# solenoid_driver.net
KiCad netlist of a schematic drawn in Altium Designer
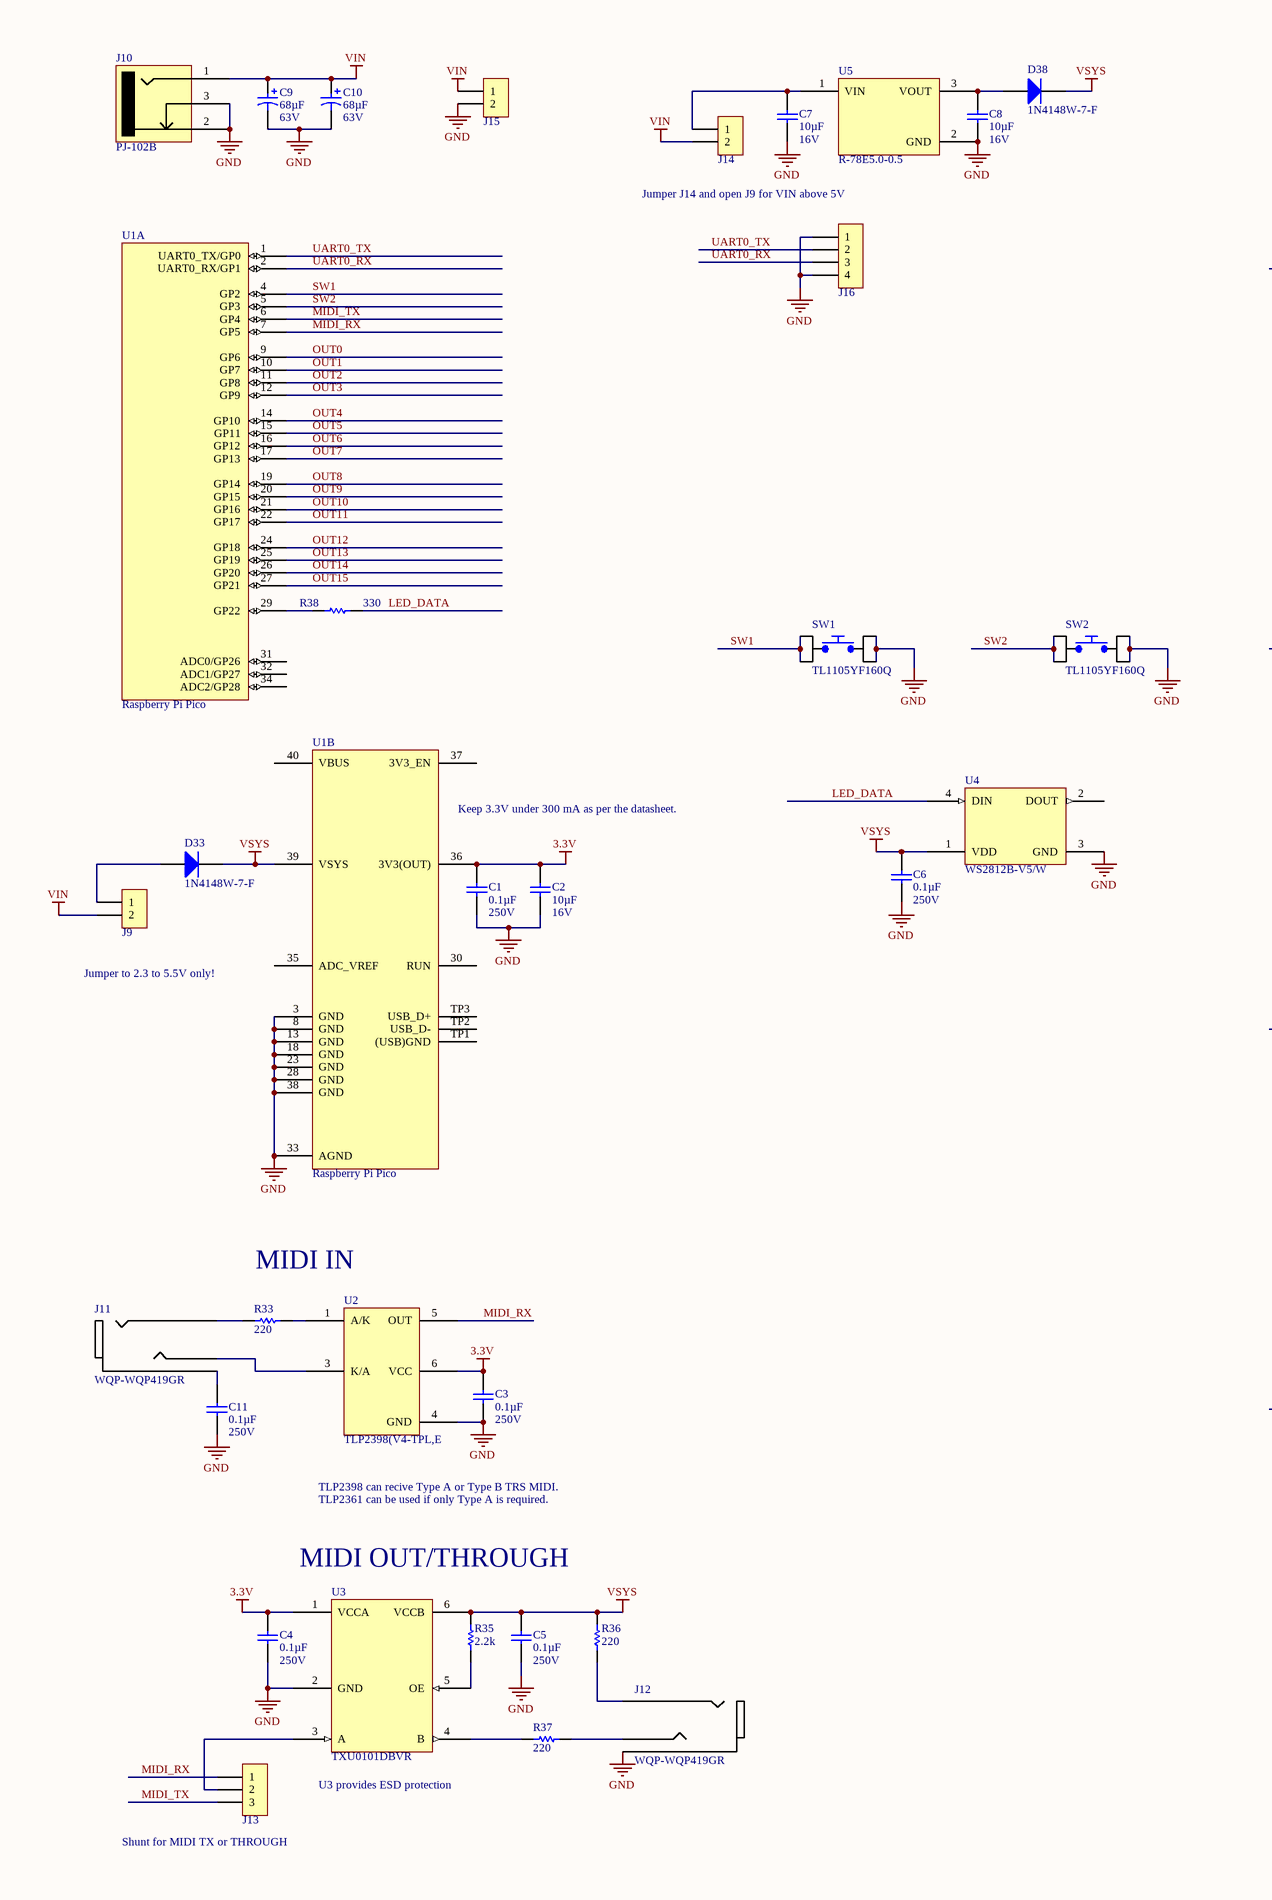
[diagram p0: solenoid_driver.SchDoc, left]
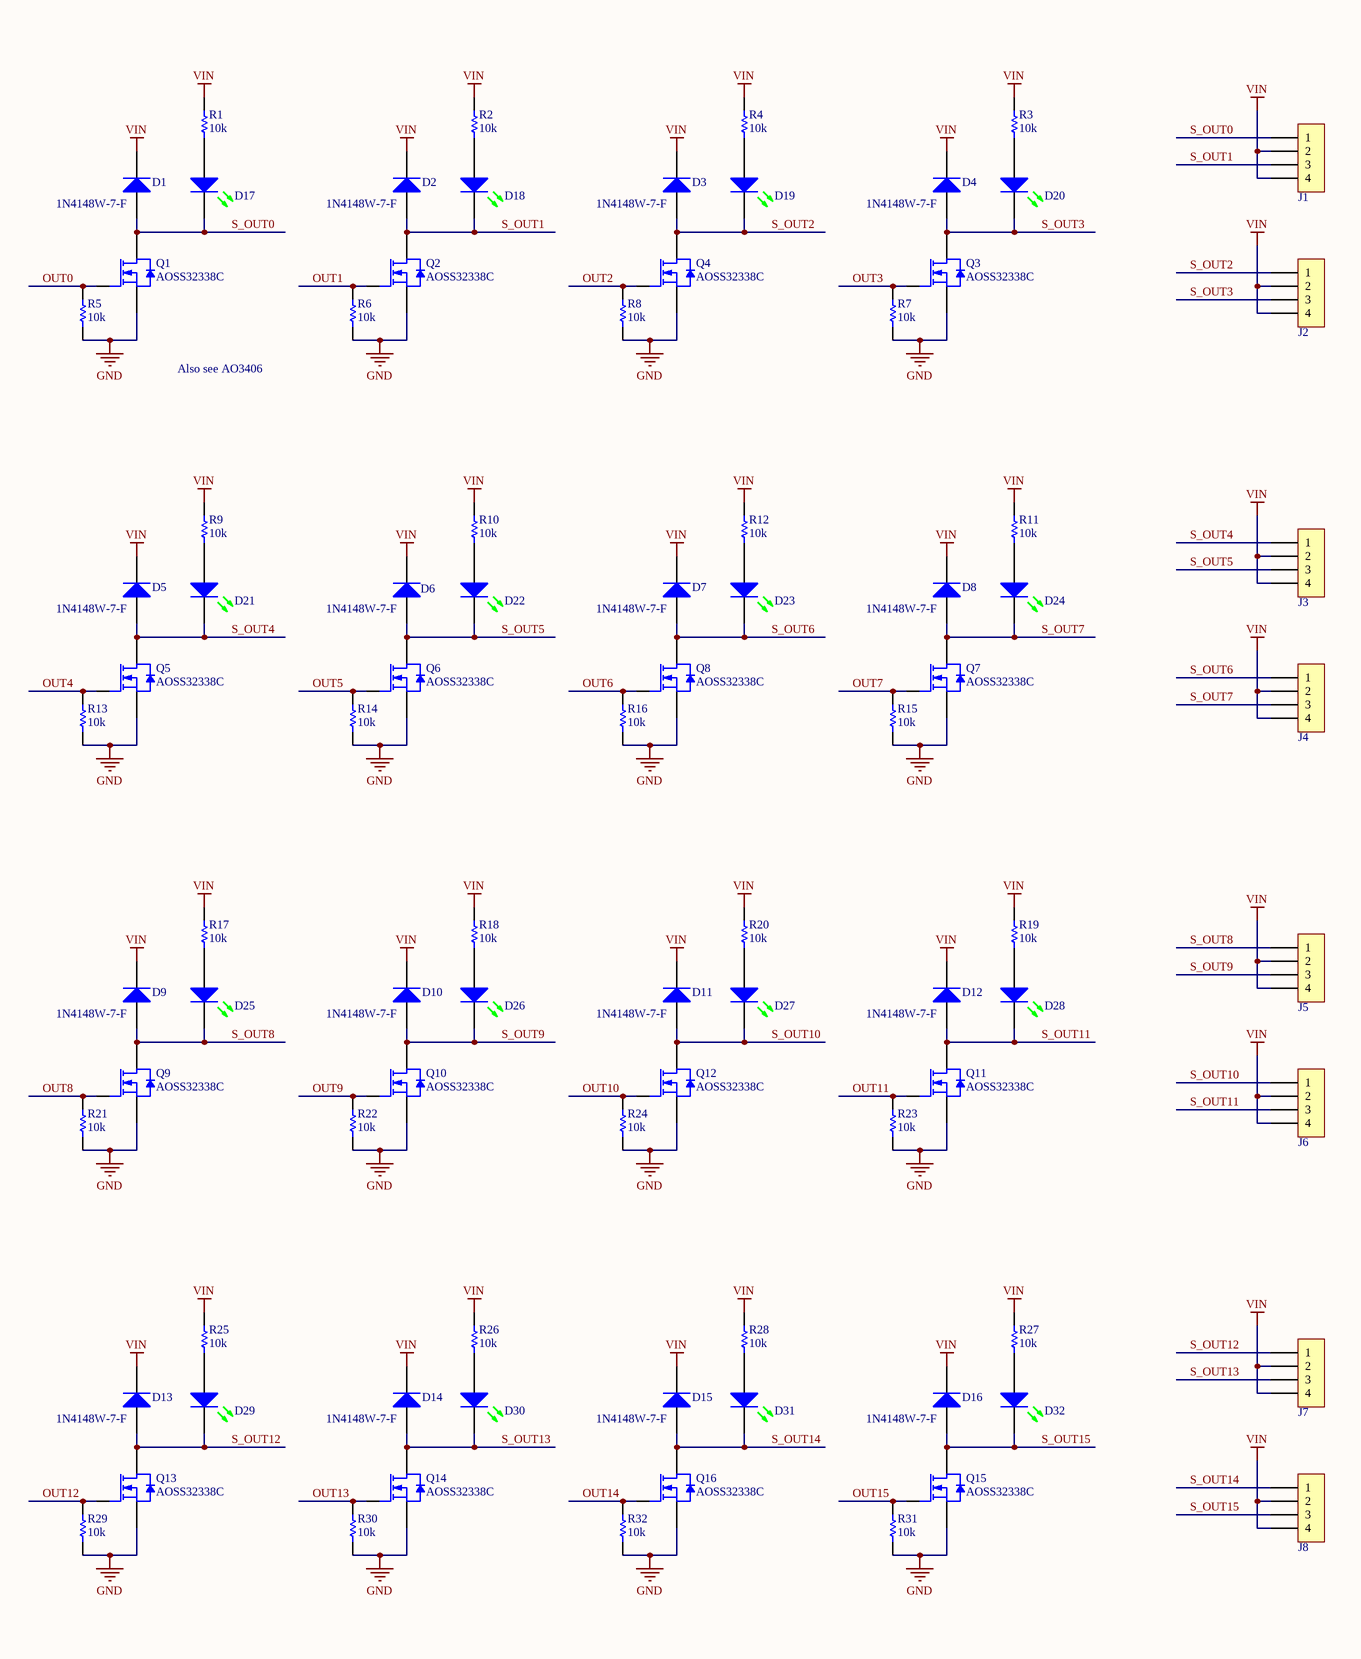
[diagram p1: solenoid_driver.SchDoc, right]

(export (version "E")
  (design (tool "Eeschema 10.0.6"))
  (components
    (comp (ref "C1")
      (value "0.1µF")
      (footprint "Chip0805")
      (description "CAP CER 0.1UF 250V 10% X7T 0805")
      (fields
        (field (name "VOLTAGE") "250V")
        (field (name "PARTNUMBER") "C2012X7T2E104K125AA")
        (field (name "MANUFACTURER") "TDK Corporation")
      )
      (libsource (lib "Passives") (part "CAP"))
    )
    (comp (ref "C2")
      (value "10µF")
      (footprint "Chip0805")
      (description "CAP CER 10UF 16V 10% X5R 0805")
      (fields
        (field (name "VOLTAGE") "16V")
        (field (name "PARTNUMBER") "C2012X5R1C106K125AC")
        (field (name "MANUFACTURER") "TDK Corporation")
      )
      (libsource (lib "Passives") (part "CAP"))
    )
    (comp (ref "C3")
      (value "0.1µF")
      (footprint "Chip0805")
      (description "CAP CER 0.1UF 250V 10% X7T 0805")
      (fields
        (field (name "VOLTAGE") "250V")
        (field (name "PARTNUMBER") "C2012X7T2E104K125AA")
        (field (name "MANUFACTURER") "TDK Corporation")
      )
      (libsource (lib "Passives") (part "CAP"))
    )
    (comp (ref "C4")
      (value "0.1µF")
      (footprint "Chip0805")
      (description "CAP CER 0.1UF 250V 10% X7T 0805")
      (fields
        (field (name "VOLTAGE") "250V")
        (field (name "PARTNUMBER") "C2012X7T2E104K125AA")
        (field (name "MANUFACTURER") "TDK Corporation")
      )
      (libsource (lib "Passives") (part "CAP"))
    )
    (comp (ref "C5")
      (value "0.1µF")
      (footprint "Chip0805")
      (description "CAP CER 0.1UF 250V 10% X7T 0805")
      (fields
        (field (name "VOLTAGE") "250V")
        (field (name "PARTNUMBER") "C2012X7T2E104K125AA")
        (field (name "MANUFACTURER") "TDK Corporation")
      )
      (libsource (lib "Passives") (part "CAP"))
    )
    (comp (ref "C6")
      (value "0.1µF")
      (footprint "Chip0805")
      (description "CAP CER 0.1UF 250V 10% X7T 0805")
      (fields
        (field (name "VOLTAGE") "250V")
        (field (name "PARTNUMBER") "C2012X7T2E104K125AA")
        (field (name "MANUFACTURER") "TDK Corporation")
      )
      (libsource (lib "Passives") (part "CAP"))
    )
    (comp (ref "C7")
      (value "10µF")
      (footprint "Chip0805")
      (description "CAP CER 10UF 16V 10% X5R 0805")
      (fields
        (field (name "VOLTAGE") "16V")
        (field (name "PARTNUMBER") "C2012X5R1C106K125AC")
        (field (name "MANUFACTURER") "TDK Corporation")
      )
      (libsource (lib "Passives") (part "CAP"))
    )
    (comp (ref "C8")
      (value "10µF")
      (footprint "Chip0805")
      (description "CAP CER 10UF 16V 10% X5R 0805")
      (fields
        (field (name "VOLTAGE") "16V")
        (field (name "PARTNUMBER") "C2012X5R1C106K125AC")
        (field (name "MANUFACTURER") "TDK Corporation")
      )
      (libsource (lib "Passives") (part "CAP"))
    )
    (comp (ref "C9")
      (value "68µF")
      (footprint "CAP_CAN_TH_3p5mmLS8")
      (description "CAP ALUM 68UF 20% 63V RADIAL")
      (fields
        (field (name "VOLTAGE RATING") "63V")
        (field (name "PARTNUMBER") "UPW1J680MPD")
        (field (name "MANUFACTURER") "Nichicon")
      )
      (libsource (lib "Passives") (part "CAP_POLARIZED"))
    )
    (comp (ref "C10")
      (value "68µF")
      (footprint "CAP_CAN_TH_3p5mmLS8")
      (description "CAP ALUM 68UF 20% 63V RADIAL")
      (fields
        (field (name "VOLTAGE RATING") "63V")
        (field (name "PARTNUMBER") "UPW1J680MPD")
        (field (name "MANUFACTURER") "Nichicon")
      )
      (libsource (lib "Passives") (part "CAP_POLARIZED"))
    )
    (comp (ref "C11")
      (value "0.1µF")
      (footprint "Chip0805")
      (description "CAP CER 0.1UF 250V 10% X7T 0805")
      (fields
        (field (name "VOLTAGE") "250V")
        (field (name "PARTNUMBER") "C2012X7T2E104K125AA")
        (field (name "MANUFACTURER") "TDK Corporation")
      )
      (libsource (lib "Passives") (part "CAP"))
    )
    (comp (ref "D1")
      (value "1N4148W-7-F")
      (footprint "SOD-123")
      (description "DIODE SWITCH 100V 0.15A SOD123")
      (fields (field (name "MANUFACTURER") "Diodes Incorporated"))
      (libsource (lib "Semiconductor") (part "DIODE"))
    )
    (comp (ref "D2")
      (value "1N4148W-7-F")
      (footprint "SOD-123")
      (description "DIODE SWITCH 100V 0.15A SOD123")
      (fields (field (name "MANUFACTURER") "Diodes Incorporated"))
      (libsource (lib "Semiconductor") (part "DIODE"))
    )
    (comp (ref "D3")
      (value "1N4148W-7-F")
      (footprint "SOD-123")
      (description "DIODE SWITCH 100V 0.15A SOD123")
      (fields (field (name "MANUFACTURER") "Diodes Incorporated"))
      (libsource (lib "Semiconductor") (part "DIODE"))
    )
    (comp (ref "D4")
      (value "1N4148W-7-F")
      (footprint "SOD-123")
      (description "DIODE SWITCH 100V 0.15A SOD123")
      (fields (field (name "MANUFACTURER") "Diodes Incorporated"))
      (libsource (lib "Semiconductor") (part "DIODE"))
    )
    (comp (ref "D5")
      (value "1N4148W-7-F")
      (footprint "SOD-123")
      (description "DIODE SWITCH 100V 0.15A SOD123")
      (fields (field (name "MANUFACTURER") "Diodes Incorporated"))
      (libsource (lib "Semiconductor") (part "DIODE"))
    )
    (comp (ref "D6")
      (value "1N4148W-7-F")
      (footprint "SOD-123")
      (description "DIODE SWITCH 100V 0.15A SOD123")
      (fields (field (name "MANUFACTURER") "Diodes Incorporated"))
      (libsource (lib "Semiconductor") (part "DIODE"))
    )
    (comp (ref "D7")
      (value "1N4148W-7-F")
      (footprint "SOD-123")
      (description "DIODE SWITCH 100V 0.15A SOD123")
      (fields (field (name "MANUFACTURER") "Diodes Incorporated"))
      (libsource (lib "Semiconductor") (part "DIODE"))
    )
    (comp (ref "D8")
      (value "1N4148W-7-F")
      (footprint "SOD-123")
      (description "DIODE SWITCH 100V 0.15A SOD123")
      (fields (field (name "MANUFACTURER") "Diodes Incorporated"))
      (libsource (lib "Semiconductor") (part "DIODE"))
    )
    (comp (ref "D9")
      (value "1N4148W-7-F")
      (footprint "SOD-123")
      (description "DIODE SWITCH 100V 0.15A SOD123")
      (fields (field (name "MANUFACTURER") "Diodes Incorporated"))
      (libsource (lib "Semiconductor") (part "DIODE"))
    )
    (comp (ref "D10")
      (value "1N4148W-7-F")
      (footprint "SOD-123")
      (description "DIODE SWITCH 100V 0.15A SOD123")
      (fields (field (name "MANUFACTURER") "Diodes Incorporated"))
      (libsource (lib "Semiconductor") (part "DIODE"))
    )
    (comp (ref "D11")
      (value "1N4148W-7-F")
      (footprint "SOD-123")
      (description "DIODE SWITCH 100V 0.15A SOD123")
      (fields (field (name "MANUFACTURER") "Diodes Incorporated"))
      (libsource (lib "Semiconductor") (part "DIODE"))
    )
    (comp (ref "D12")
      (value "1N4148W-7-F")
      (footprint "SOD-123")
      (description "DIODE SWITCH 100V 0.15A SOD123")
      (fields (field (name "MANUFACTURER") "Diodes Incorporated"))
      (libsource (lib "Semiconductor") (part "DIODE"))
    )
    (comp (ref "D13")
      (value "1N4148W-7-F")
      (footprint "SOD-123")
      (description "DIODE SWITCH 100V 0.15A SOD123")
      (fields (field (name "MANUFACTURER") "Diodes Incorporated"))
      (libsource (lib "Semiconductor") (part "DIODE"))
    )
    (comp (ref "D14")
      (value "1N4148W-7-F")
      (footprint "SOD-123")
      (description "DIODE SWITCH 100V 0.15A SOD123")
      (fields (field (name "MANUFACTURER") "Diodes Incorporated"))
      (libsource (lib "Semiconductor") (part "DIODE"))
    )
    (comp (ref "D15")
      (value "1N4148W-7-F")
      (footprint "SOD-123")
      (description "DIODE SWITCH 100V 0.15A SOD123")
      (fields (field (name "MANUFACTURER") "Diodes Incorporated"))
      (libsource (lib "Semiconductor") (part "DIODE"))
    )
    (comp (ref "D16")
      (value "1N4148W-7-F")
      (footprint "SOD-123")
      (description "DIODE SWITCH 100V 0.15A SOD123")
      (fields (field (name "MANUFACTURER") "Diodes Incorporated"))
      (libsource (lib "Semiconductor") (part "DIODE"))
    )
    (comp (ref "D17")
      (value "GREEN")
      (footprint "LED0603")
      (description "LED GREEN CLEAR THIN 0603 SMD")
      (fields (field (name "PARTNUMBER") "LTST-C191GKT") (field (name "MANUFACTURER") "Lite-On Inc"))
      (libsource (lib "Optoelectronics") (part "LED_GREEN"))
    )
    (comp (ref "D18")
      (value "GREEN")
      (footprint "LED0603")
      (description "LED GREEN CLEAR THIN 0603 SMD")
      (fields (field (name "PARTNUMBER") "LTST-C191GKT") (field (name "MANUFACTURER") "Lite-On Inc"))
      (libsource (lib "Optoelectronics") (part "LED_GREEN"))
    )
    (comp (ref "D19")
      (value "GREEN")
      (footprint "LED0603")
      (description "LED GREEN CLEAR THIN 0603 SMD")
      (fields (field (name "PARTNUMBER") "LTST-C191GKT") (field (name "MANUFACTURER") "Lite-On Inc"))
      (libsource (lib "Optoelectronics") (part "LED_GREEN"))
    )
    (comp (ref "D20")
      (value "GREEN")
      (footprint "LED0603")
      (description "LED GREEN CLEAR THIN 0603 SMD")
      (fields (field (name "PARTNUMBER") "LTST-C191GKT") (field (name "MANUFACTURER") "Lite-On Inc"))
      (libsource (lib "Optoelectronics") (part "LED_GREEN"))
    )
    (comp (ref "D21")
      (value "GREEN")
      (footprint "LED0603")
      (description "LED GREEN CLEAR THIN 0603 SMD")
      (fields (field (name "PARTNUMBER") "LTST-C191GKT") (field (name "MANUFACTURER") "Lite-On Inc"))
      (libsource (lib "Optoelectronics") (part "LED_GREEN"))
    )
    (comp (ref "D22")
      (value "GREEN")
      (footprint "LED0603")
      (description "LED GREEN CLEAR THIN 0603 SMD")
      (fields (field (name "PARTNUMBER") "LTST-C191GKT") (field (name "MANUFACTURER") "Lite-On Inc"))
      (libsource (lib "Optoelectronics") (part "LED_GREEN"))
    )
    (comp (ref "D23")
      (value "GREEN")
      (footprint "LED0603")
      (description "LED GREEN CLEAR THIN 0603 SMD")
      (fields (field (name "PARTNUMBER") "LTST-C191GKT") (field (name "MANUFACTURER") "Lite-On Inc"))
      (libsource (lib "Optoelectronics") (part "LED_GREEN"))
    )
    (comp (ref "D24")
      (value "GREEN")
      (footprint "LED0603")
      (description "LED GREEN CLEAR THIN 0603 SMD")
      (fields (field (name "PARTNUMBER") "LTST-C191GKT") (field (name "MANUFACTURER") "Lite-On Inc"))
      (libsource (lib "Optoelectronics") (part "LED_GREEN"))
    )
    (comp (ref "D25")
      (value "GREEN")
      (footprint "LED0603")
      (description "LED GREEN CLEAR THIN 0603 SMD")
      (fields (field (name "PARTNUMBER") "LTST-C191GKT") (field (name "MANUFACTURER") "Lite-On Inc"))
      (libsource (lib "Optoelectronics") (part "LED_GREEN"))
    )
    (comp (ref "D26")
      (value "GREEN")
      (footprint "LED0603")
      (description "LED GREEN CLEAR THIN 0603 SMD")
      (fields (field (name "PARTNUMBER") "LTST-C191GKT") (field (name "MANUFACTURER") "Lite-On Inc"))
      (libsource (lib "Optoelectronics") (part "LED_GREEN"))
    )
    (comp (ref "D27")
      (value "GREEN")
      (footprint "LED0603")
      (description "LED GREEN CLEAR THIN 0603 SMD")
      (fields (field (name "PARTNUMBER") "LTST-C191GKT") (field (name "MANUFACTURER") "Lite-On Inc"))
      (libsource (lib "Optoelectronics") (part "LED_GREEN"))
    )
    (comp (ref "D28")
      (value "GREEN")
      (footprint "LED0603")
      (description "LED GREEN CLEAR THIN 0603 SMD")
      (fields (field (name "PARTNUMBER") "LTST-C191GKT") (field (name "MANUFACTURER") "Lite-On Inc"))
      (libsource (lib "Optoelectronics") (part "LED_GREEN"))
    )
    (comp (ref "D29")
      (value "GREEN")
      (footprint "LED0603")
      (description "LED GREEN CLEAR THIN 0603 SMD")
      (fields (field (name "PARTNUMBER") "LTST-C191GKT") (field (name "MANUFACTURER") "Lite-On Inc"))
      (libsource (lib "Optoelectronics") (part "LED_GREEN"))
    )
    (comp (ref "D30")
      (value "GREEN")
      (footprint "LED0603")
      (description "LED GREEN CLEAR THIN 0603 SMD")
      (fields (field (name "PARTNUMBER") "LTST-C191GKT") (field (name "MANUFACTURER") "Lite-On Inc"))
      (libsource (lib "Optoelectronics") (part "LED_GREEN"))
    )
    (comp (ref "D31")
      (value "GREEN")
      (footprint "LED0603")
      (description "LED GREEN CLEAR THIN 0603 SMD")
      (fields (field (name "PARTNUMBER") "LTST-C191GKT") (field (name "MANUFACTURER") "Lite-On Inc"))
      (libsource (lib "Optoelectronics") (part "LED_GREEN"))
    )
    (comp (ref "D32")
      (value "GREEN")
      (footprint "LED0603")
      (description "LED GREEN CLEAR THIN 0603 SMD")
      (fields (field (name "PARTNUMBER") "LTST-C191GKT") (field (name "MANUFACTURER") "Lite-On Inc"))
      (libsource (lib "Optoelectronics") (part "LED_GREEN"))
    )
    (comp (ref "D33")
      (value "1N4148W-7-F")
      (footprint "SOD-123")
      (description "DIODE SWITCH 100V 0.15A SOD123")
      (fields (field (name "MANUFACTURER") "Diodes Incorporated"))
      (libsource (lib "Semiconductor") (part "DIODE"))
    )
    (comp (ref "D38")
      (value "1N4148W-7-F")
      (footprint "SOD-123")
      (description "DIODE SWITCH 100V 0.15A SOD123")
      (fields (field (name "MANUFACTURER") "Diodes Incorporated"))
      (libsource (lib "Semiconductor") (part "DIODE"))
    )
    (comp (ref "J1")
      (value "691210910004")
      (footprint "WURTH_691210910004")
      (description "TERM BLOCK 4P HORIZON 2.54MM PCB")
      (fields (field (name "MANUFACTURER") "Würth Elektronik"))
      (libsource (lib "Connectors") (part "HEADER_1x4"))
    )
    (comp (ref "J2")
      (value "691210910004")
      (footprint "WURTH_691210910004")
      (description "TERM BLOCK 4P HORIZON 2.54MM PCB")
      (fields (field (name "MANUFACTURER") "Würth Elektronik"))
      (libsource (lib "Connectors") (part "HEADER_1x4"))
    )
    (comp (ref "J3")
      (value "691210910004")
      (footprint "WURTH_691210910004")
      (description "TERM BLOCK 4P HORIZON 2.54MM PCB")
      (fields (field (name "MANUFACTURER") "Würth Elektronik"))
      (libsource (lib "Connectors") (part "HEADER_1x4"))
    )
    (comp (ref "J4")
      (value "691210910004")
      (footprint "WURTH_691210910004")
      (description "TERM BLOCK 4P HORIZON 2.54MM PCB")
      (fields (field (name "MANUFACTURER") "Würth Elektronik"))
      (libsource (lib "Connectors") (part "HEADER_1x4"))
    )
    (comp (ref "J5")
      (value "691210910004")
      (footprint "WURTH_691210910004")
      (description "TERM BLOCK 4P HORIZON 2.54MM PCB")
      (fields (field (name "MANUFACTURER") "Würth Elektronik"))
      (libsource (lib "Connectors") (part "HEADER_1x4"))
    )
    (comp (ref "J6")
      (value "691210910004")
      (footprint "WURTH_691210910004")
      (description "TERM BLOCK 4P HORIZON 2.54MM PCB")
      (fields (field (name "MANUFACTURER") "Würth Elektronik"))
      (libsource (lib "Connectors") (part "HEADER_1x4"))
    )
    (comp (ref "J7")
      (value "691210910004")
      (footprint "WURTH_691210910004")
      (description "TERM BLOCK 4P HORIZON 2.54MM PCB")
      (fields (field (name "MANUFACTURER") "Würth Elektronik"))
      (libsource (lib "Connectors") (part "HEADER_1x4"))
    )
    (comp (ref "J8")
      (value "691210910004")
      (footprint "WURTH_691210910004")
      (description "TERM BLOCK 4P HORIZON 2.54MM PCB")
      (fields (field (name "MANUFACTURER") "Würth Elektronik"))
      (libsource (lib "Connectors") (part "HEADER_1x4"))
    )
    (comp (ref "J9")
      (value "3-644456-2")
      (footprint "TE_3-644456-2")
      (description "CONN HEADER VERT 2POS .100 TIN")
      (fields (field (name "MANUFACTURER") "TE Connectivity"))
      (libsource (lib "Connectors") (part "HEADER_1x2"))
    )
    (comp (ref "J10")
      (value "PJ-102B")
      (footprint "CUI_PJ-102B")
      (description "CONN PWR JACK 2.5X5.5MM SOLDER")
      (fields (field (name "MANUFACTURER") "CUI Devices"))
      (libsource (lib "Connectors") (part "DC_POWER_JACK"))
    )
    (comp (ref "J11")
      (value "WQP-WQP419GR")
      (footprint "PJ366ST")
      (description "CONN 3.5mm VIRTICAL STEREO")
      (fields (field (name "MANUFACTURER") "QingPu"))
      (libsource (lib "Connectors") (part "PJ366ST"))
    )
    (comp (ref "J12")
      (value "WQP-WQP419GR")
      (footprint "PJ366ST")
      (description "CONN 3.5mm VIRTICAL STEREO")
      (fields (field (name "MANUFACTURER") "QingPu"))
      (libsource (lib "Connectors") (part "PJ366ST"))
    )
    (comp (ref "J13")
      (value "3-644456-3")
      (footprint "TE_3-644456-3")
      (description "CONN HEADER VERT 3POS .100 TIN")
      (fields (field (name "MANUFACTURER") "TE Connectivity"))
      (libsource (lib "Connectors") (part "HEADER_1x3"))
    )
    (comp (ref "J14")
      (value "3-644456-2")
      (footprint "TE_3-644456-2")
      (description "CONN HEADER VERT 2POS .100 TIN")
      (fields (field (name "MANUFACTURER") "TE Connectivity"))
      (libsource (lib "Connectors") (part "HEADER_1x2"))
    )
    (comp (ref "J15")
      (value "691210910002")
      (footprint "WURTH_691210910002")
      (description "TERM BLOCK 2P HORIZON 2.54MM PCB")
      (fields (field (name "MANUFACTURER") "Würth Elektronik"))
      (libsource (lib "Connectors") (part "HEADER_1x2"))
    )
    (comp (ref "J16")
      (value "0533980471")
      (footprint "Molex_0533980471")
      (description "CONN HEADER SMD 4POS 1.25MM")
      (fields (field (name "MANUFACTURER") "Molex"))
      (libsource (lib "Connectors") (part "HEADER_1x4"))
    )
    (comp (ref "Q1")
      (value "AOSS32338C")
      (footprint "SOT23-3N")
      (description "MOSFET N-CH 30V 4A SOT23-3")
      (fields (field (name "MANUFACTURER") "Alpha & Omega Semiconductor Inc."))
      (libsource (lib "Semiconductor") (part "FET_N_ENHANCEMENT"))
    )
    (comp (ref "Q2")
      (value "AOSS32338C")
      (footprint "SOT23-3N")
      (description "MOSFET N-CH 30V 4A SOT23-3")
      (fields (field (name "MANUFACTURER") "Alpha & Omega Semiconductor Inc."))
      (libsource (lib "Semiconductor") (part "FET_N_ENHANCEMENT"))
    )
    (comp (ref "Q3")
      (value "AOSS32338C")
      (footprint "SOT23-3N")
      (description "MOSFET N-CH 30V 4A SOT23-3")
      (fields (field (name "MANUFACTURER") "Alpha & Omega Semiconductor Inc."))
      (libsource (lib "Semiconductor") (part "FET_N_ENHANCEMENT"))
    )
    (comp (ref "Q4")
      (value "AOSS32338C")
      (footprint "SOT23-3N")
      (description "MOSFET N-CH 30V 4A SOT23-3")
      (fields (field (name "MANUFACTURER") "Alpha & Omega Semiconductor Inc."))
      (libsource (lib "Semiconductor") (part "FET_N_ENHANCEMENT"))
    )
    (comp (ref "Q5")
      (value "AOSS32338C")
      (footprint "SOT23-3N")
      (description "MOSFET N-CH 30V 4A SOT23-3")
      (fields (field (name "MANUFACTURER") "Alpha & Omega Semiconductor Inc."))
      (libsource (lib "Semiconductor") (part "FET_N_ENHANCEMENT"))
    )
    (comp (ref "Q6")
      (value "AOSS32338C")
      (footprint "SOT23-3N")
      (description "MOSFET N-CH 30V 4A SOT23-3")
      (fields (field (name "MANUFACTURER") "Alpha & Omega Semiconductor Inc."))
      (libsource (lib "Semiconductor") (part "FET_N_ENHANCEMENT"))
    )
    (comp (ref "Q7")
      (value "AOSS32338C")
      (footprint "SOT23-3N")
      (description "MOSFET N-CH 30V 4A SOT23-3")
      (fields (field (name "MANUFACTURER") "Alpha & Omega Semiconductor Inc."))
      (libsource (lib "Semiconductor") (part "FET_N_ENHANCEMENT"))
    )
    (comp (ref "Q8")
      (value "AOSS32338C")
      (footprint "SOT23-3N")
      (description "MOSFET N-CH 30V 4A SOT23-3")
      (fields (field (name "MANUFACTURER") "Alpha & Omega Semiconductor Inc."))
      (libsource (lib "Semiconductor") (part "FET_N_ENHANCEMENT"))
    )
    (comp (ref "Q9")
      (value "AOSS32338C")
      (footprint "SOT23-3N")
      (description "MOSFET N-CH 30V 4A SOT23-3")
      (fields (field (name "MANUFACTURER") "Alpha & Omega Semiconductor Inc."))
      (libsource (lib "Semiconductor") (part "FET_N_ENHANCEMENT"))
    )
    (comp (ref "Q10")
      (value "AOSS32338C")
      (footprint "SOT23-3N")
      (description "MOSFET N-CH 30V 4A SOT23-3")
      (fields (field (name "MANUFACTURER") "Alpha & Omega Semiconductor Inc."))
      (libsource (lib "Semiconductor") (part "FET_N_ENHANCEMENT"))
    )
    (comp (ref "Q11")
      (value "AOSS32338C")
      (footprint "SOT23-3N")
      (description "MOSFET N-CH 30V 4A SOT23-3")
      (fields (field (name "MANUFACTURER") "Alpha & Omega Semiconductor Inc."))
      (libsource (lib "Semiconductor") (part "FET_N_ENHANCEMENT"))
    )
    (comp (ref "Q12")
      (value "AOSS32338C")
      (footprint "SOT23-3N")
      (description "MOSFET N-CH 30V 4A SOT23-3")
      (fields (field (name "MANUFACTURER") "Alpha & Omega Semiconductor Inc."))
      (libsource (lib "Semiconductor") (part "FET_N_ENHANCEMENT"))
    )
    (comp (ref "Q13")
      (value "AOSS32338C")
      (footprint "SOT23-3N")
      (description "MOSFET N-CH 30V 4A SOT23-3")
      (fields (field (name "MANUFACTURER") "Alpha & Omega Semiconductor Inc."))
      (libsource (lib "Semiconductor") (part "FET_N_ENHANCEMENT"))
    )
    (comp (ref "Q14")
      (value "AOSS32338C")
      (footprint "SOT23-3N")
      (description "MOSFET N-CH 30V 4A SOT23-3")
      (fields (field (name "MANUFACTURER") "Alpha & Omega Semiconductor Inc."))
      (libsource (lib "Semiconductor") (part "FET_N_ENHANCEMENT"))
    )
    (comp (ref "Q15")
      (value "AOSS32338C")
      (footprint "SOT23-3N")
      (description "MOSFET N-CH 30V 4A SOT23-3")
      (fields (field (name "MANUFACTURER") "Alpha & Omega Semiconductor Inc."))
      (libsource (lib "Semiconductor") (part "FET_N_ENHANCEMENT"))
    )
    (comp (ref "Q16")
      (value "AOSS32338C")
      (footprint "SOT23-3N")
      (description "MOSFET N-CH 30V 4A SOT23-3")
      (fields (field (name "MANUFACTURER") "Alpha & Omega Semiconductor Inc."))
      (libsource (lib "Semiconductor") (part "FET_N_ENHANCEMENT"))
    )
    (comp (ref "R1")
      (value "10k")
      (footprint "Chip0805")
      (description "RES 10.0K OHM 1/8W 1% 0805 SMD")
      (fields (field (name "PARTNUMBER") "CRCW080510K0FKEA") (field (name "MANUFACTURER") "Vishay Dale"))
      (libsource (lib "Passives") (part "RES"))
    )
    (comp (ref "R2")
      (value "10k")
      (footprint "Chip0805")
      (description "RES 10.0K OHM 1/8W 1% 0805 SMD")
      (fields (field (name "PARTNUMBER") "CRCW080510K0FKEA") (field (name "MANUFACTURER") "Vishay Dale"))
      (libsource (lib "Passives") (part "RES"))
    )
    (comp (ref "R3")
      (value "10k")
      (footprint "Chip0805")
      (description "RES 10.0K OHM 1/8W 1% 0805 SMD")
      (fields (field (name "PARTNUMBER") "CRCW080510K0FKEA") (field (name "MANUFACTURER") "Vishay Dale"))
      (libsource (lib "Passives") (part "RES"))
    )
    (comp (ref "R4")
      (value "10k")
      (footprint "Chip0805")
      (description "RES 10.0K OHM 1/8W 1% 0805 SMD")
      (fields (field (name "PARTNUMBER") "CRCW080510K0FKEA") (field (name "MANUFACTURER") "Vishay Dale"))
      (libsource (lib "Passives") (part "RES"))
    )
    (comp (ref "R5")
      (value "10k")
      (footprint "Chip0805")
      (description "RES 10.0K OHM 1/8W 1% 0805 SMD")
      (fields (field (name "PARTNUMBER") "CRCW080510K0FKEA") (field (name "MANUFACTURER") "Vishay Dale"))
      (libsource (lib "Passives") (part "RES"))
    )
    (comp (ref "R6")
      (value "10k")
      (footprint "Chip0805")
      (description "RES 10.0K OHM 1/8W 1% 0805 SMD")
      (fields (field (name "PARTNUMBER") "CRCW080510K0FKEA") (field (name "MANUFACTURER") "Vishay Dale"))
      (libsource (lib "Passives") (part "RES"))
    )
    (comp (ref "R7")
      (value "10k")
      (footprint "Chip0805")
      (description "RES 10.0K OHM 1/8W 1% 0805 SMD")
      (fields (field (name "PARTNUMBER") "CRCW080510K0FKEA") (field (name "MANUFACTURER") "Vishay Dale"))
      (libsource (lib "Passives") (part "RES"))
    )
    (comp (ref "R8")
      (value "10k")
      (footprint "Chip0805")
      (description "RES 10.0K OHM 1/8W 1% 0805 SMD")
      (fields (field (name "PARTNUMBER") "CRCW080510K0FKEA") (field (name "MANUFACTURER") "Vishay Dale"))
      (libsource (lib "Passives") (part "RES"))
    )
    (comp (ref "R9")
      (value "10k")
      (footprint "Chip0805")
      (description "RES 10.0K OHM 1/8W 1% 0805 SMD")
      (fields (field (name "PARTNUMBER") "CRCW080510K0FKEA") (field (name "MANUFACTURER") "Vishay Dale"))
      (libsource (lib "Passives") (part "RES"))
    )
    (comp (ref "R10")
      (value "10k")
      (footprint "Chip0805")
      (description "RES 10.0K OHM 1/8W 1% 0805 SMD")
      (fields (field (name "PARTNUMBER") "CRCW080510K0FKEA") (field (name "MANUFACTURER") "Vishay Dale"))
      (libsource (lib "Passives") (part "RES"))
    )
    (comp (ref "R11")
      (value "10k")
      (footprint "Chip0805")
      (description "RES 10.0K OHM 1/8W 1% 0805 SMD")
      (fields (field (name "PARTNUMBER") "CRCW080510K0FKEA") (field (name "MANUFACTURER") "Vishay Dale"))
      (libsource (lib "Passives") (part "RES"))
    )
    (comp (ref "R12")
      (value "10k")
      (footprint "Chip0805")
      (description "RES 10.0K OHM 1/8W 1% 0805 SMD")
      (fields (field (name "PARTNUMBER") "CRCW080510K0FKEA") (field (name "MANUFACTURER") "Vishay Dale"))
      (libsource (lib "Passives") (part "RES"))
    )
    (comp (ref "R13")
      (value "10k")
      (footprint "Chip0805")
      (description "RES 10.0K OHM 1/8W 1% 0805 SMD")
      (fields (field (name "PARTNUMBER") "CRCW080510K0FKEA") (field (name "MANUFACTURER") "Vishay Dale"))
      (libsource (lib "Passives") (part "RES"))
    )
    (comp (ref "R14")
      (value "10k")
      (footprint "Chip0805")
      (description "RES 10.0K OHM 1/8W 1% 0805 SMD")
      (fields (field (name "PARTNUMBER") "CRCW080510K0FKEA") (field (name "MANUFACTURER") "Vishay Dale"))
      (libsource (lib "Passives") (part "RES"))
    )
    (comp (ref "R15")
      (value "10k")
      (footprint "Chip0805")
      (description "RES 10.0K OHM 1/8W 1% 0805 SMD")
      (fields (field (name "PARTNUMBER") "CRCW080510K0FKEA") (field (name "MANUFACTURER") "Vishay Dale"))
      (libsource (lib "Passives") (part "RES"))
    )
    (comp (ref "R16")
      (value "10k")
      (footprint "Chip0805")
      (description "RES 10.0K OHM 1/8W 1% 0805 SMD")
      (fields (field (name "PARTNUMBER") "CRCW080510K0FKEA") (field (name "MANUFACTURER") "Vishay Dale"))
      (libsource (lib "Passives") (part "RES"))
    )
    (comp (ref "R17")
      (value "10k")
      (footprint "Chip0805")
      (description "RES 10.0K OHM 1/8W 1% 0805 SMD")
      (fields (field (name "PARTNUMBER") "CRCW080510K0FKEA") (field (name "MANUFACTURER") "Vishay Dale"))
      (libsource (lib "Passives") (part "RES"))
    )
    (comp (ref "R18")
      (value "10k")
      (footprint "Chip0805")
      (description "RES 10.0K OHM 1/8W 1% 0805 SMD")
      (fields (field (name "PARTNUMBER") "CRCW080510K0FKEA") (field (name "MANUFACTURER") "Vishay Dale"))
      (libsource (lib "Passives") (part "RES"))
    )
    (comp (ref "R19")
      (value "10k")
      (footprint "Chip0805")
      (description "RES 10.0K OHM 1/8W 1% 0805 SMD")
      (fields (field (name "PARTNUMBER") "CRCW080510K0FKEA") (field (name "MANUFACTURER") "Vishay Dale"))
      (libsource (lib "Passives") (part "RES"))
    )
    (comp (ref "R20")
      (value "10k")
      (footprint "Chip0805")
      (description "RES 10.0K OHM 1/8W 1% 0805 SMD")
      (fields (field (name "PARTNUMBER") "CRCW080510K0FKEA") (field (name "MANUFACTURER") "Vishay Dale"))
      (libsource (lib "Passives") (part "RES"))
    )
    (comp (ref "R21")
      (value "10k")
      (footprint "Chip0805")
      (description "RES 10.0K OHM 1/8W 1% 0805 SMD")
      (fields (field (name "PARTNUMBER") "CRCW080510K0FKEA") (field (name "MANUFACTURER") "Vishay Dale"))
      (libsource (lib "Passives") (part "RES"))
    )
    (comp (ref "R22")
      (value "10k")
      (footprint "Chip0805")
      (description "RES 10.0K OHM 1/8W 1% 0805 SMD")
      (fields (field (name "PARTNUMBER") "CRCW080510K0FKEA") (field (name "MANUFACTURER") "Vishay Dale"))
      (libsource (lib "Passives") (part "RES"))
    )
    (comp (ref "R23")
      (value "10k")
      (footprint "Chip0805")
      (description "RES 10.0K OHM 1/8W 1% 0805 SMD")
      (fields (field (name "PARTNUMBER") "CRCW080510K0FKEA") (field (name "MANUFACTURER") "Vishay Dale"))
      (libsource (lib "Passives") (part "RES"))
    )
    (comp (ref "R24")
      (value "10k")
      (footprint "Chip0805")
      (description "RES 10.0K OHM 1/8W 1% 0805 SMD")
      (fields (field (name "PARTNUMBER") "CRCW080510K0FKEA") (field (name "MANUFACTURER") "Vishay Dale"))
      (libsource (lib "Passives") (part "RES"))
    )
    (comp (ref "R25")
      (value "10k")
      (footprint "Chip0805")
      (description "RES 10.0K OHM 1/8W 1% 0805 SMD")
      (fields (field (name "PARTNUMBER") "CRCW080510K0FKEA") (field (name "MANUFACTURER") "Vishay Dale"))
      (libsource (lib "Passives") (part "RES"))
    )
    (comp (ref "R26")
      (value "10k")
      (footprint "Chip0805")
      (description "RES 10.0K OHM 1/8W 1% 0805 SMD")
      (fields (field (name "PARTNUMBER") "CRCW080510K0FKEA") (field (name "MANUFACTURER") "Vishay Dale"))
      (libsource (lib "Passives") (part "RES"))
    )
    (comp (ref "R27")
      (value "10k")
      (footprint "Chip0805")
      (description "RES 10.0K OHM 1/8W 1% 0805 SMD")
      (fields (field (name "PARTNUMBER") "CRCW080510K0FKEA") (field (name "MANUFACTURER") "Vishay Dale"))
      (libsource (lib "Passives") (part "RES"))
    )
    (comp (ref "R28")
      (value "10k")
      (footprint "Chip0805")
      (description "RES 10.0K OHM 1/8W 1% 0805 SMD")
      (fields (field (name "PARTNUMBER") "CRCW080510K0FKEA") (field (name "MANUFACTURER") "Vishay Dale"))
      (libsource (lib "Passives") (part "RES"))
    )
    (comp (ref "R29")
      (value "10k")
      (footprint "Chip0805")
      (description "RES 10.0K OHM 1/8W 1% 0805 SMD")
      (fields (field (name "PARTNUMBER") "CRCW080510K0FKEA") (field (name "MANUFACTURER") "Vishay Dale"))
      (libsource (lib "Passives") (part "RES"))
    )
    (comp (ref "R30")
      (value "10k")
      (footprint "Chip0805")
      (description "RES 10.0K OHM 1/8W 1% 0805 SMD")
      (fields (field (name "PARTNUMBER") "CRCW080510K0FKEA") (field (name "MANUFACTURER") "Vishay Dale"))
      (libsource (lib "Passives") (part "RES"))
    )
    (comp (ref "R31")
      (value "10k")
      (footprint "Chip0805")
      (description "RES 10.0K OHM 1/8W 1% 0805 SMD")
      (fields (field (name "PARTNUMBER") "CRCW080510K0FKEA") (field (name "MANUFACTURER") "Vishay Dale"))
      (libsource (lib "Passives") (part "RES"))
    )
    (comp (ref "R32")
      (value "10k")
      (footprint "Chip0805")
      (description "RES 10.0K OHM 1/8W 1% 0805 SMD")
      (fields (field (name "PARTNUMBER") "CRCW080510K0FKEA") (field (name "MANUFACTURER") "Vishay Dale"))
      (libsource (lib "Passives") (part "RES"))
    )
    (comp (ref "R33")
      (value "220")
      (footprint "Chip0805")
      (description "RES 220 OHM 1/8W 1% 0805 SMD")
      (fields (field (name "PARTNUMBER") "CRCW0805220RFKEA") (field (name "MANUFACTURER") "Vishay Dale"))
      (libsource (lib "Passives") (part "RES"))
    )
    (comp (ref "R35")
      (value "2.2k")
      (footprint "Chip0805")
      (description "RES 2.20K OHM 1/8W 1% 0805 SMD")
      (fields (field (name "PARTNUMBER") "CRCW08052K20FKEA") (field (name "MANUFACTURER") "Vishay Dale"))
      (libsource (lib "Passives") (part "RES"))
    )
    (comp (ref "R36")
      (value "220")
      (footprint "Chip0805")
      (description "RES 220 OHM 1/8W 1% 0805 SMD")
      (fields (field (name "PARTNUMBER") "CRCW0805220RFKEA") (field (name "MANUFACTURER") "Vishay Dale"))
      (libsource (lib "Passives") (part "RES"))
    )
    (comp (ref "R37")
      (value "220")
      (footprint "Chip0805")
      (description "RES 220 OHM 1/8W 1% 0805 SMD")
      (fields (field (name "PARTNUMBER") "CRCW0805220RFKEA") (field (name "MANUFACTURER") "Vishay Dale"))
      (libsource (lib "Passives") (part "RES"))
    )
    (comp (ref "R38")
      (value "330")
      (footprint "Chip0805")
      (description "RES 330 OHM 1/8W 1% 0805 SMD")
      (fields (field (name "PARTNUMBER") "CRCW0805330RFKEA") (field (name "MANUFACTURER") "Vishay Dale"))
      (libsource (lib "Passives") (part "RES"))
    )
    (comp (ref "SW1")
      (value "TL1105YF160Q")
      (footprint "E-Switch_TL1105YF")
      (description "SWITCH TACTILE SPST-NO 0.05A 12V")
      (fields (field (name "MANUFACTURER") "E-Switch"))
      (libsource (lib "Switches") (part "SWITCH_SPST_4PIN"))
    )
    (comp (ref "SW2")
      (value "TL1105YF160Q")
      (footprint "E-Switch_TL1105YF")
      (description "SWITCH TACTILE SPST-NO 0.05A 12V")
      (fields (field (name "MANUFACTURER") "E-Switch"))
      (libsource (lib "Switches") (part "SWITCH_SPST_4PIN"))
    )
    (comp (ref "U1")
      (value "Raspberry Pi Pico")
      (footprint "RASPBERRY_PI_PICO")
      (description "RASPBERRY PI PICO RP2040 BOARD")
      (fields (field (name "MANUFACTURER PART NUMBER") "SC0915") (field (name "MANUFACTURER") "Raspberry Pi"))
      (libsource (lib "ICs") (part "PI_PICO_SC0915"))
    )
    (comp (ref "U2")
      (value "TLP2398(V4-TPL,E")
      (footprint "6-SO_NO_PIN_2")
      (description "High Speed Optocouplers SO6")
      (fields (field (name "MANUFACTURER") "Toshiba"))
      (libsource (lib "ICs") (part "TOSHIBA_TLP2398"))
    )
    (comp (ref "U3")
      (value "TXU0101DBVR")
      (footprint "SOT-23-6N")
      (description "IC XLTR VL UNIDIR SOT-23-6")
      (fields (field (name "MANUFACTURER") "Texas Instruments"))
      (libsource (lib "ICs") (part "TI_TXU0101"))
    )
    (comp (ref "U4")
      (value "WS2812B-V5/W")
      (footprint "WS2812B")
      (description "Addressable RGB LED")
      (fields (field (name "MANUFACTURER") "Worldsemi"))
      (libsource (lib "Optoelectronics") (part "WORLDSEMI_WS2812B"))
    )
    (comp (ref "U5")
      (value "R-78E5.0-0.5")
      (footprint "3-SIP_Module")
      (description "DC DC CONVERTER 5V 3W")
      (fields (field (name "MANUFACTURER") "Recom Power"))
      (libsource (lib "ICs") (part "3-SIP_Module"))
    )
  )
  (nets
    (net (code "1") (name "/LED_DATA") (class "Default")
      (node (ref "R38") (pin "2") (pinfunction "2_2") (pintype "passive"))
      (node (ref "U4") (pin "4") (pinfunction "DIN_4") (pintype "input"))
    )
    (net (code "2") (name "/MIDI_RX") (class "Default")
      (node (ref "J13") (pin "1") (pinfunction "1_1") (pintype "passive"))
      (node (ref "U1") (pin "7") (pinfunction "GP5_7") (pintype "bidirectional"))
      (node (ref "U2") (pin "5") (pinfunction "OUT_5") (pintype "passive"))
    )
    (net (code "3") (name "/MIDI_TX") (class "Default")
      (node (ref "J13") (pin "3") (pinfunction "3_3") (pintype "passive"))
      (node (ref "U1") (pin "6") (pinfunction "GP4_6") (pintype "bidirectional"))
    )
    (net (code "4") (name "/OUT0") (class "Default")
      (node (ref "Q1") (pin "1") (pinfunction "G_1") (pintype "passive"))
      (node (ref "R5") (pin "1") (pinfunction "1_1") (pintype "passive"))
      (node (ref "U1") (pin "9") (pinfunction "GP6_9") (pintype "bidirectional"))
    )
    (net (code "5") (name "/OUT1") (class "Default")
      (node (ref "Q2") (pin "1") (pinfunction "G_1") (pintype "passive"))
      (node (ref "R6") (pin "1") (pinfunction "1_1") (pintype "passive"))
      (node (ref "U1") (pin "10") (pinfunction "GP7_10") (pintype "bidirectional"))
    )
    (net (code "6") (name "/OUT2") (class "Default")
      (node (ref "Q4") (pin "1") (pinfunction "G_1") (pintype "passive"))
      (node (ref "R8") (pin "1") (pinfunction "1_1") (pintype "passive"))
      (node (ref "U1") (pin "11") (pinfunction "GP8_11") (pintype "bidirectional"))
    )
    (net (code "7") (name "/OUT3") (class "Default")
      (node (ref "Q3") (pin "1") (pinfunction "G_1") (pintype "passive"))
      (node (ref "R7") (pin "1") (pinfunction "1_1") (pintype "passive"))
      (node (ref "U1") (pin "12") (pinfunction "GP9_12") (pintype "bidirectional"))
    )
    (net (code "8") (name "/OUT4") (class "Default")
      (node (ref "Q5") (pin "1") (pinfunction "G_1") (pintype "passive"))
      (node (ref "R13") (pin "1") (pinfunction "1_1") (pintype "passive"))
      (node (ref "U1") (pin "14") (pinfunction "GP10_14") (pintype "bidirectional"))
    )
    (net (code "9") (name "/OUT5") (class "Default")
      (node (ref "Q6") (pin "1") (pinfunction "G_1") (pintype "passive"))
      (node (ref "R14") (pin "1") (pinfunction "1_1") (pintype "passive"))
      (node (ref "U1") (pin "15") (pinfunction "GP11_15") (pintype "bidirectional"))
    )
    (net (code "10") (name "/OUT6") (class "Default")
      (node (ref "Q8") (pin "1") (pinfunction "G_1") (pintype "passive"))
      (node (ref "R16") (pin "1") (pinfunction "1_1") (pintype "passive"))
      (node (ref "U1") (pin "16") (pinfunction "GP12_16") (pintype "bidirectional"))
    )
    (net (code "11") (name "/OUT7") (class "Default")
      (node (ref "Q7") (pin "1") (pinfunction "G_1") (pintype "passive"))
      (node (ref "R15") (pin "1") (pinfunction "1_1") (pintype "passive"))
      (node (ref "U1") (pin "17") (pinfunction "GP13_17") (pintype "bidirectional"))
    )
    (net (code "12") (name "/OUT8") (class "Default")
      (node (ref "Q9") (pin "1") (pinfunction "G_1") (pintype "passive"))
      (node (ref "R21") (pin "1") (pinfunction "1_1") (pintype "passive"))
      (node (ref "U1") (pin "19") (pinfunction "GP14_19") (pintype "bidirectional"))
    )
    (net (code "13") (name "/OUT9") (class "Default")
      (node (ref "Q10") (pin "1") (pinfunction "G_1") (pintype "passive"))
      (node (ref "R22") (pin "1") (pinfunction "1_1") (pintype "passive"))
      (node (ref "U1") (pin "20") (pinfunction "GP15_20") (pintype "bidirectional"))
    )
    (net (code "14") (name "/OUT10") (class "Default")
      (node (ref "Q12") (pin "1") (pinfunction "G_1") (pintype "passive"))
      (node (ref "R24") (pin "1") (pinfunction "1_1") (pintype "passive"))
      (node (ref "U1") (pin "21") (pinfunction "GP16_21") (pintype "bidirectional"))
    )
    (net (code "15") (name "/OUT11") (class "Default")
      (node (ref "Q11") (pin "1") (pinfunction "G_1") (pintype "passive"))
      (node (ref "R23") (pin "1") (pinfunction "1_1") (pintype "passive"))
      (node (ref "U1") (pin "22") (pinfunction "GP17_22") (pintype "bidirectional"))
    )
    (net (code "16") (name "/OUT12") (class "Default")
      (node (ref "Q13") (pin "1") (pinfunction "G_1") (pintype "passive"))
      (node (ref "R29") (pin "1") (pinfunction "1_1") (pintype "passive"))
      (node (ref "U1") (pin "24") (pinfunction "GP18_24") (pintype "bidirectional"))
    )
    (net (code "17") (name "/OUT13") (class "Default")
      (node (ref "Q14") (pin "1") (pinfunction "G_1") (pintype "passive"))
      (node (ref "R30") (pin "1") (pinfunction "1_1") (pintype "passive"))
      (node (ref "U1") (pin "25") (pinfunction "GP19_25") (pintype "bidirectional"))
    )
    (net (code "18") (name "/OUT14") (class "Default")
      (node (ref "Q16") (pin "1") (pinfunction "G_1") (pintype "passive"))
      (node (ref "R32") (pin "1") (pinfunction "1_1") (pintype "passive"))
      (node (ref "U1") (pin "26") (pinfunction "GP20_26") (pintype "bidirectional"))
    )
    (net (code "19") (name "/OUT15") (class "Default")
      (node (ref "Q15") (pin "1") (pinfunction "G_1") (pintype "passive"))
      (node (ref "R31") (pin "1") (pinfunction "1_1") (pintype "passive"))
      (node (ref "U1") (pin "27") (pinfunction "GP21_27") (pintype "bidirectional"))
    )
    (net (code "20") (name "/SW1") (class "Default")
      (node (ref "SW1") (pin "1") (pinfunction "1_1") (pintype "passive"))
      (node (ref "SW1") (pin "2") (pinfunction "2_2") (pintype "passive"))
      (node (ref "U1") (pin "4") (pinfunction "GP2_4") (pintype "bidirectional"))
    )
    (net (code "21") (name "/SW2") (class "Default")
      (node (ref "SW2") (pin "1") (pinfunction "1_1") (pintype "passive"))
      (node (ref "SW2") (pin "2") (pinfunction "2_2") (pintype "passive"))
      (node (ref "U1") (pin "5") (pinfunction "GP3_5") (pintype "bidirectional"))
    )
    (net (code "22") (name "/S_OUT0") (class "Default")
      (node (ref "D1") (pin "2") (pinfunction "A_2") (pintype "passive"))
      (node (ref "D17") (pin "2") (pinfunction "C_2") (pintype "passive"))
      (node (ref "J1") (pin "1") (pinfunction "1_1") (pintype "passive"))
      (node (ref "Q1") (pin "3") (pinfunction "D_3") (pintype "passive"))
    )
    (net (code "23") (name "/S_OUT1") (class "Default")
      (node (ref "D18") (pin "2") (pinfunction "C_2") (pintype "passive"))
      (node (ref "D2") (pin "2") (pinfunction "A_2") (pintype "passive"))
      (node (ref "J1") (pin "3") (pinfunction "3_3") (pintype "passive"))
      (node (ref "Q2") (pin "3") (pinfunction "D_3") (pintype "passive"))
    )
    (net (code "24") (name "/S_OUT2") (class "Default")
      (node (ref "D19") (pin "2") (pinfunction "C_2") (pintype "passive"))
      (node (ref "D3") (pin "2") (pinfunction "A_2") (pintype "passive"))
      (node (ref "J2") (pin "1") (pinfunction "1_1") (pintype "passive"))
      (node (ref "Q4") (pin "3") (pinfunction "D_3") (pintype "passive"))
    )
    (net (code "25") (name "/S_OUT3") (class "Default")
      (node (ref "D20") (pin "2") (pinfunction "C_2") (pintype "passive"))
      (node (ref "D4") (pin "2") (pinfunction "A_2") (pintype "passive"))
      (node (ref "J2") (pin "3") (pinfunction "3_3") (pintype "passive"))
      (node (ref "Q3") (pin "3") (pinfunction "D_3") (pintype "passive"))
    )
    (net (code "26") (name "/S_OUT4") (class "Default")
      (node (ref "D21") (pin "2") (pinfunction "C_2") (pintype "passive"))
      (node (ref "D5") (pin "2") (pinfunction "A_2") (pintype "passive"))
      (node (ref "J3") (pin "1") (pinfunction "1_1") (pintype "passive"))
      (node (ref "Q5") (pin "3") (pinfunction "D_3") (pintype "passive"))
    )
    (net (code "27") (name "/S_OUT5") (class "Default")
      (node (ref "D22") (pin "2") (pinfunction "C_2") (pintype "passive"))
      (node (ref "D6") (pin "2") (pinfunction "A_2") (pintype "passive"))
      (node (ref "J3") (pin "3") (pinfunction "3_3") (pintype "passive"))
      (node (ref "Q6") (pin "3") (pinfunction "D_3") (pintype "passive"))
    )
    (net (code "28") (name "/S_OUT6") (class "Default")
      (node (ref "D23") (pin "2") (pinfunction "C_2") (pintype "passive"))
      (node (ref "D7") (pin "2") (pinfunction "A_2") (pintype "passive"))
      (node (ref "J4") (pin "1") (pinfunction "1_1") (pintype "passive"))
      (node (ref "Q8") (pin "3") (pinfunction "D_3") (pintype "passive"))
    )
    (net (code "29") (name "/S_OUT7") (class "Default")
      (node (ref "D24") (pin "2") (pinfunction "C_2") (pintype "passive"))
      (node (ref "D8") (pin "2") (pinfunction "A_2") (pintype "passive"))
      (node (ref "J4") (pin "3") (pinfunction "3_3") (pintype "passive"))
      (node (ref "Q7") (pin "3") (pinfunction "D_3") (pintype "passive"))
    )
    (net (code "30") (name "/S_OUT8") (class "Default")
      (node (ref "D25") (pin "2") (pinfunction "C_2") (pintype "passive"))
      (node (ref "D9") (pin "2") (pinfunction "A_2") (pintype "passive"))
      (node (ref "J5") (pin "1") (pinfunction "1_1") (pintype "passive"))
      (node (ref "Q9") (pin "3") (pinfunction "D_3") (pintype "passive"))
    )
    (net (code "31") (name "/S_OUT9") (class "Default")
      (node (ref "D10") (pin "2") (pinfunction "A_2") (pintype "passive"))
      (node (ref "D26") (pin "2") (pinfunction "C_2") (pintype "passive"))
      (node (ref "J5") (pin "3") (pinfunction "3_3") (pintype "passive"))
      (node (ref "Q10") (pin "3") (pinfunction "D_3") (pintype "passive"))
    )
    (net (code "32") (name "/S_OUT10") (class "Default")
      (node (ref "D11") (pin "2") (pinfunction "A_2") (pintype "passive"))
      (node (ref "D27") (pin "2") (pinfunction "C_2") (pintype "passive"))
      (node (ref "J6") (pin "1") (pinfunction "1_1") (pintype "passive"))
      (node (ref "Q12") (pin "3") (pinfunction "D_3") (pintype "passive"))
    )
    (net (code "33") (name "/S_OUT11") (class "Default")
      (node (ref "D12") (pin "2") (pinfunction "A_2") (pintype "passive"))
      (node (ref "D28") (pin "2") (pinfunction "C_2") (pintype "passive"))
      (node (ref "J6") (pin "3") (pinfunction "3_3") (pintype "passive"))
      (node (ref "Q11") (pin "3") (pinfunction "D_3") (pintype "passive"))
    )
    (net (code "34") (name "/S_OUT12") (class "Default")
      (node (ref "D13") (pin "2") (pinfunction "A_2") (pintype "passive"))
      (node (ref "D29") (pin "2") (pinfunction "C_2") (pintype "passive"))
      (node (ref "J7") (pin "1") (pinfunction "1_1") (pintype "passive"))
      (node (ref "Q13") (pin "3") (pinfunction "D_3") (pintype "passive"))
    )
    (net (code "35") (name "/S_OUT13") (class "Default")
      (node (ref "D14") (pin "2") (pinfunction "A_2") (pintype "passive"))
      (node (ref "D30") (pin "2") (pinfunction "C_2") (pintype "passive"))
      (node (ref "J7") (pin "3") (pinfunction "3_3") (pintype "passive"))
      (node (ref "Q14") (pin "3") (pinfunction "D_3") (pintype "passive"))
    )
    (net (code "36") (name "/S_OUT14") (class "Default")
      (node (ref "D15") (pin "2") (pinfunction "A_2") (pintype "passive"))
      (node (ref "D31") (pin "2") (pinfunction "C_2") (pintype "passive"))
      (node (ref "J8") (pin "1") (pinfunction "1_1") (pintype "passive"))
      (node (ref "Q16") (pin "3") (pinfunction "D_3") (pintype "passive"))
    )
    (net (code "37") (name "/S_OUT15") (class "Default")
      (node (ref "D16") (pin "2") (pinfunction "A_2") (pintype "passive"))
      (node (ref "D32") (pin "2") (pinfunction "C_2") (pintype "passive"))
      (node (ref "J8") (pin "3") (pinfunction "3_3") (pintype "passive"))
      (node (ref "Q15") (pin "3") (pinfunction "D_3") (pintype "passive"))
    )
    (net (code "38") (name "/UART0_RX") (class "Default")
      (node (ref "J16") (pin "3") (pinfunction "3_3") (pintype "passive"))
      (node (ref "U1") (pin "2") (pinfunction "UART0_RX/GP1_2") (pintype "bidirectional"))
    )
    (net (code "39") (name "/UART0_TX") (class "Default")
      (node (ref "J16") (pin "2") (pinfunction "2_2") (pintype "passive"))
      (node (ref "U1") (pin "1") (pinfunction "UART0_TX/GP0_1") (pintype "bidirectional"))
    )
    (net (code "40") (name "3.3V") (class "Default")
      (node (ref "C1") (pin "2") (pinfunction "2_2") (pintype "passive"))
      (node (ref "C2") (pin "2") (pinfunction "2_2") (pintype "passive"))
      (node (ref "C3") (pin "2") (pinfunction "2_2") (pintype "passive"))
      (node (ref "C4") (pin "2") (pinfunction "2_2") (pintype "passive"))
      (node (ref "U1") (pin "36") (pinfunction "3V3(OUT)_36") (pintype "passive"))
      (node (ref "U2") (pin "6") (pinfunction "VCC_6") (pintype "passive"))
      (node (ref "U3") (pin "1") (pinfunction "VCCA_1") (pintype "passive"))
    )
    (net (code "41") (name "GND") (class "Default")
      (node (ref "C1") (pin "1") (pinfunction "1_1") (pintype "passive"))
      (node (ref "C10") (pin "2") (pinfunction "2_2") (pintype "passive"))
      (node (ref "C11") (pin "1") (pinfunction "1_1") (pintype "passive"))
      (node (ref "C2") (pin "1") (pinfunction "1_1") (pintype "passive"))
      (node (ref "C3") (pin "1") (pinfunction "1_1") (pintype "passive"))
      (node (ref "C4") (pin "1") (pinfunction "1_1") (pintype "passive"))
      (node (ref "C5") (pin "1") (pinfunction "1_1") (pintype "passive"))
      (node (ref "C6") (pin "1") (pinfunction "1_1") (pintype "passive"))
      (node (ref "C7") (pin "1") (pinfunction "1_1") (pintype "passive"))
      (node (ref "C8") (pin "1") (pinfunction "1_1") (pintype "passive"))
      (node (ref "C9") (pin "2") (pinfunction "2_2") (pintype "passive"))
      (node (ref "J10") (pin "2") (pinfunction "2_2") (pintype "passive"))
      (node (ref "J10") (pin "3") (pinfunction "3_3") (pintype "passive"))
      (node (ref "J12") (pin "1") (pinfunction "1_1") (pintype "passive"))
      (node (ref "J15") (pin "2") (pinfunction "2_2") (pintype "passive"))
      (node (ref "J16") (pin "1") (pinfunction "1_1") (pintype "passive"))
      (node (ref "J16") (pin "4") (pinfunction "4_4") (pintype "passive"))
      (node (ref "Q1") (pin "2") (pinfunction "S_2") (pintype "passive"))
      (node (ref "Q10") (pin "2") (pinfunction "S_2") (pintype "passive"))
      (node (ref "Q11") (pin "2") (pinfunction "S_2") (pintype "passive"))
      (node (ref "Q12") (pin "2") (pinfunction "S_2") (pintype "passive"))
      (node (ref "Q13") (pin "2") (pinfunction "S_2") (pintype "passive"))
      (node (ref "Q14") (pin "2") (pinfunction "S_2") (pintype "passive"))
      (node (ref "Q15") (pin "2") (pinfunction "S_2") (pintype "passive"))
      (node (ref "Q16") (pin "2") (pinfunction "S_2") (pintype "passive"))
      (node (ref "Q2") (pin "2") (pinfunction "S_2") (pintype "passive"))
      (node (ref "Q3") (pin "2") (pinfunction "S_2") (pintype "passive"))
      (node (ref "Q4") (pin "2") (pinfunction "S_2") (pintype "passive"))
      (node (ref "Q5") (pin "2") (pinfunction "S_2") (pintype "passive"))
      (node (ref "Q6") (pin "2") (pinfunction "S_2") (pintype "passive"))
      (node (ref "Q7") (pin "2") (pinfunction "S_2") (pintype "passive"))
      (node (ref "Q8") (pin "2") (pinfunction "S_2") (pintype "passive"))
      (node (ref "Q9") (pin "2") (pinfunction "S_2") (pintype "passive"))
      (node (ref "R13") (pin "2") (pinfunction "2_2") (pintype "passive"))
      (node (ref "R14") (pin "2") (pinfunction "2_2") (pintype "passive"))
      (node (ref "R15") (pin "2") (pinfunction "2_2") (pintype "passive"))
      (node (ref "R16") (pin "2") (pinfunction "2_2") (pintype "passive"))
      (node (ref "R21") (pin "2") (pinfunction "2_2") (pintype "passive"))
      (node (ref "R22") (pin "2") (pinfunction "2_2") (pintype "passive"))
      (node (ref "R23") (pin "2") (pinfunction "2_2") (pintype "passive"))
      (node (ref "R24") (pin "2") (pinfunction "2_2") (pintype "passive"))
      (node (ref "R29") (pin "2") (pinfunction "2_2") (pintype "passive"))
      (node (ref "R30") (pin "2") (pinfunction "2_2") (pintype "passive"))
      (node (ref "R31") (pin "2") (pinfunction "2_2") (pintype "passive"))
      (node (ref "R32") (pin "2") (pinfunction "2_2") (pintype "passive"))
      (node (ref "R5") (pin "2") (pinfunction "2_2") (pintype "passive"))
      (node (ref "R6") (pin "2") (pinfunction "2_2") (pintype "passive"))
      (node (ref "R7") (pin "2") (pinfunction "2_2") (pintype "passive"))
      (node (ref "R8") (pin "2") (pinfunction "2_2") (pintype "passive"))
      (node (ref "SW1") (pin "3") (pinfunction "3_3") (pintype "passive"))
      (node (ref "SW1") (pin "4") (pinfunction "4_4") (pintype "passive"))
      (node (ref "SW2") (pin "3") (pinfunction "3_3") (pintype "passive"))
      (node (ref "SW2") (pin "4") (pinfunction "4_4") (pintype "passive"))
      (node (ref "U1") (pin "13") (pinfunction "GND_13") (pintype "passive"))
      (node (ref "U1") (pin "18") (pinfunction "GND_18") (pintype "passive"))
      (node (ref "U1") (pin "23") (pinfunction "GND_23") (pintype "passive"))
      (node (ref "U1") (pin "28") (pinfunction "GND_28") (pintype "passive"))
      (node (ref "U1") (pin "3") (pinfunction "GND_3") (pintype "passive"))
      (node (ref "U1") (pin "33") (pinfunction "AGND_33") (pintype "passive"))
      (node (ref "U1") (pin "38") (pinfunction "GND_38") (pintype "passive"))
      (node (ref "U1") (pin "8") (pinfunction "GND_8") (pintype "passive"))
      (node (ref "U2") (pin "4") (pinfunction "GND_4") (pintype "passive"))
      (node (ref "U3") (pin "2") (pinfunction "GND_2") (pintype "passive"))
      (node (ref "U4") (pin "3") (pinfunction "GND_3") (pintype "passive"))
      (node (ref "U5") (pin "2") (pinfunction "GND_2") (pintype "passive"))
    )
    (net (code "42") (name "Net-(C11-Pad2)") (class "Default")
      (node (ref "C11") (pin "2") (pinfunction "2_2") (pintype "passive"))
      (node (ref "J11") (pin "1") (pinfunction "1_1") (pintype "passive"))
    )
    (net (code "43") (name "Net-(D17-A)") (class "Default")
      (node (ref "D17") (pin "1") (pinfunction "A_1") (pintype "passive"))
      (node (ref "R1") (pin "2") (pinfunction "2_2") (pintype "passive"))
    )
    (net (code "44") (name "Net-(D18-A)") (class "Default")
      (node (ref "D18") (pin "1") (pinfunction "A_1") (pintype "passive"))
      (node (ref "R2") (pin "2") (pinfunction "2_2") (pintype "passive"))
    )
    (net (code "45") (name "Net-(D19-A)") (class "Default")
      (node (ref "D19") (pin "1") (pinfunction "A_1") (pintype "passive"))
      (node (ref "R4") (pin "2") (pinfunction "2_2") (pintype "passive"))
    )
    (net (code "46") (name "Net-(D20-A)") (class "Default")
      (node (ref "D20") (pin "1") (pinfunction "A_1") (pintype "passive"))
      (node (ref "R3") (pin "2") (pinfunction "2_2") (pintype "passive"))
    )
    (net (code "47") (name "Net-(D21-A)") (class "Default")
      (node (ref "D21") (pin "1") (pinfunction "A_1") (pintype "passive"))
      (node (ref "R9") (pin "2") (pinfunction "2_2") (pintype "passive"))
    )
    (net (code "48") (name "Net-(D22-A)") (class "Default")
      (node (ref "D22") (pin "1") (pinfunction "A_1") (pintype "passive"))
      (node (ref "R10") (pin "2") (pinfunction "2_2") (pintype "passive"))
    )
    (net (code "49") (name "Net-(D23-A)") (class "Default")
      (node (ref "D23") (pin "1") (pinfunction "A_1") (pintype "passive"))
      (node (ref "R12") (pin "2") (pinfunction "2_2") (pintype "passive"))
    )
    (net (code "50") (name "Net-(D24-A)") (class "Default")
      (node (ref "D24") (pin "1") (pinfunction "A_1") (pintype "passive"))
      (node (ref "R11") (pin "2") (pinfunction "2_2") (pintype "passive"))
    )
    (net (code "51") (name "Net-(D25-A)") (class "Default")
      (node (ref "D25") (pin "1") (pinfunction "A_1") (pintype "passive"))
      (node (ref "R17") (pin "2") (pinfunction "2_2") (pintype "passive"))
    )
    (net (code "52") (name "Net-(D26-A)") (class "Default")
      (node (ref "D26") (pin "1") (pinfunction "A_1") (pintype "passive"))
      (node (ref "R18") (pin "2") (pinfunction "2_2") (pintype "passive"))
    )
    (net (code "53") (name "Net-(D27-A)") (class "Default")
      (node (ref "D27") (pin "1") (pinfunction "A_1") (pintype "passive"))
      (node (ref "R20") (pin "2") (pinfunction "2_2") (pintype "passive"))
    )
    (net (code "54") (name "Net-(D28-A)") (class "Default")
      (node (ref "D28") (pin "1") (pinfunction "A_1") (pintype "passive"))
      (node (ref "R19") (pin "2") (pinfunction "2_2") (pintype "passive"))
    )
    (net (code "55") (name "Net-(D29-A)") (class "Default")
      (node (ref "D29") (pin "1") (pinfunction "A_1") (pintype "passive"))
      (node (ref "R25") (pin "2") (pinfunction "2_2") (pintype "passive"))
    )
    (net (code "56") (name "Net-(D30-A)") (class "Default")
      (node (ref "D30") (pin "1") (pinfunction "A_1") (pintype "passive"))
      (node (ref "R26") (pin "2") (pinfunction "2_2") (pintype "passive"))
    )
    (net (code "57") (name "Net-(D31-A)") (class "Default")
      (node (ref "D31") (pin "1") (pinfunction "A_1") (pintype "passive"))
      (node (ref "R28") (pin "2") (pinfunction "2_2") (pintype "passive"))
    )
    (net (code "58") (name "Net-(D32-A)") (class "Default")
      (node (ref "D32") (pin "1") (pinfunction "A_1") (pintype "passive"))
      (node (ref "R27") (pin "2") (pinfunction "2_2") (pintype "passive"))
    )
    (net (code "59") (name "Net-(D33-A)") (class "Default")
      (node (ref "D33") (pin "2") (pinfunction "A_2") (pintype "passive"))
      (node (ref "J9") (pin "1") (pinfunction "1_1") (pintype "passive"))
    )
    (net (code "60") (name "Net-(D38-A)") (class "Default")
      (node (ref "C8") (pin "2") (pinfunction "2_2") (pintype "passive"))
      (node (ref "D38") (pin "2") (pinfunction "A_2") (pintype "passive"))
      (node (ref "U5") (pin "3") (pinfunction "VOUT_3") (pintype "passive"))
    )
    (net (code "61") (name "Net-(J11-Pad2)") (class "Default")
      (node (ref "J11") (pin "2") (pinfunction "2_2") (pintype "passive"))
      (node (ref "R33") (pin "1") (pinfunction "1_1") (pintype "passive"))
    )
    (net (code "62") (name "Net-(J12-Pad2)") (class "Default")
      (node (ref "J12") (pin "2") (pinfunction "2_2") (pintype "passive"))
      (node (ref "R36") (pin "1") (pinfunction "1_1") (pintype "passive"))
    )
    (net (code "63") (name "Net-(J12-Pad3)") (class "Default")
      (node (ref "J12") (pin "3") (pinfunction "3_3") (pintype "passive"))
      (node (ref "R37") (pin "2") (pinfunction "2_2") (pintype "passive"))
    )
    (net (code "64") (name "Net-(U1A-GP22)") (class "Default")
      (node (ref "R38") (pin "1") (pinfunction "1_1") (pintype "passive"))
      (node (ref "U1") (pin "29") (pinfunction "GP22_29") (pintype "bidirectional"))
    )
    (net (code "65") (name "Net-(U2-A{slash}K)") (class "Default")
      (node (ref "R33") (pin "2") (pinfunction "2_2") (pintype "passive"))
      (node (ref "U2") (pin "1") (pinfunction "A/K_1") (pintype "passive"))
    )
    (net (code "66") (name "Net-(U2-K{slash}A)") (class "Default")
      (node (ref "J11") (pin "3") (pinfunction "3_3") (pintype "passive"))
      (node (ref "U2") (pin "3") (pinfunction "K/A_3") (pintype "passive"))
    )
    (net (code "67") (name "Net-(U3-A)") (class "Default")
      (node (ref "J13") (pin "2") (pinfunction "2_2") (pintype "passive"))
      (node (ref "U3") (pin "3") (pinfunction "A_3") (pintype "input"))
    )
    (net (code "68") (name "Net-(U3-B)") (class "Default")
      (node (ref "R37") (pin "1") (pinfunction "1_1") (pintype "passive"))
      (node (ref "U3") (pin "4") (pinfunction "B_4") (pintype "output"))
    )
    (net (code "69") (name "Net-(U3-OE)") (class "Default")
      (node (ref "R35") (pin "1") (pinfunction "1_1") (pintype "passive"))
      (node (ref "U3") (pin "5") (pinfunction "OE_5") (pintype "input"))
    )
    (net (code "70") (name "Net-(U5-VIN)") (class "Default")
      (node (ref "C7") (pin "2") (pinfunction "2_2") (pintype "passive"))
      (node (ref "J14") (pin "1") (pinfunction "1_1") (pintype "passive"))
      (node (ref "U5") (pin "1") (pinfunction "VIN_1") (pintype "passive"))
    )
    (net (code "71") (name "VIN") (class "Default")
      (node (ref "C10") (pin "1") (pinfunction "1_1") (pintype "passive"))
      (node (ref "C9") (pin "1") (pinfunction "1_1") (pintype "passive"))
      (node (ref "D1") (pin "1") (pinfunction "C_1") (pintype "passive"))
      (node (ref "D10") (pin "1") (pinfunction "C_1") (pintype "passive"))
      (node (ref "D11") (pin "1") (pinfunction "C_1") (pintype "passive"))
      (node (ref "D12") (pin "1") (pinfunction "C_1") (pintype "passive"))
      (node (ref "D13") (pin "1") (pinfunction "C_1") (pintype "passive"))
      (node (ref "D14") (pin "1") (pinfunction "C_1") (pintype "passive"))
      (node (ref "D15") (pin "1") (pinfunction "C_1") (pintype "passive"))
      (node (ref "D16") (pin "1") (pinfunction "C_1") (pintype "passive"))
      (node (ref "D2") (pin "1") (pinfunction "C_1") (pintype "passive"))
      (node (ref "D3") (pin "1") (pinfunction "C_1") (pintype "passive"))
      (node (ref "D4") (pin "1") (pinfunction "C_1") (pintype "passive"))
      (node (ref "D5") (pin "1") (pinfunction "C_1") (pintype "passive"))
      (node (ref "D6") (pin "1") (pinfunction "C_1") (pintype "passive"))
      (node (ref "D7") (pin "1") (pinfunction "C_1") (pintype "passive"))
      (node (ref "D8") (pin "1") (pinfunction "C_1") (pintype "passive"))
      (node (ref "D9") (pin "1") (pinfunction "C_1") (pintype "passive"))
      (node (ref "J1") (pin "2") (pinfunction "2_2") (pintype "passive"))
      (node (ref "J1") (pin "4") (pinfunction "4_4") (pintype "passive"))
      (node (ref "J10") (pin "1") (pinfunction "1_1") (pintype "passive"))
      (node (ref "J14") (pin "2") (pinfunction "2_2") (pintype "passive"))
      (node (ref "J15") (pin "1") (pinfunction "1_1") (pintype "passive"))
      (node (ref "J2") (pin "2") (pinfunction "2_2") (pintype "passive"))
      (node (ref "J2") (pin "4") (pinfunction "4_4") (pintype "passive"))
      (node (ref "J3") (pin "2") (pinfunction "2_2") (pintype "passive"))
      (node (ref "J3") (pin "4") (pinfunction "4_4") (pintype "passive"))
      (node (ref "J4") (pin "2") (pinfunction "2_2") (pintype "passive"))
      (node (ref "J4") (pin "4") (pinfunction "4_4") (pintype "passive"))
      (node (ref "J5") (pin "2") (pinfunction "2_2") (pintype "passive"))
      (node (ref "J5") (pin "4") (pinfunction "4_4") (pintype "passive"))
      (node (ref "J6") (pin "2") (pinfunction "2_2") (pintype "passive"))
      (node (ref "J6") (pin "4") (pinfunction "4_4") (pintype "passive"))
      (node (ref "J7") (pin "2") (pinfunction "2_2") (pintype "passive"))
      (node (ref "J7") (pin "4") (pinfunction "4_4") (pintype "passive"))
      (node (ref "J8") (pin "2") (pinfunction "2_2") (pintype "passive"))
      (node (ref "J8") (pin "4") (pinfunction "4_4") (pintype "passive"))
      (node (ref "J9") (pin "2") (pinfunction "2_2") (pintype "passive"))
      (node (ref "R1") (pin "1") (pinfunction "1_1") (pintype "passive"))
      (node (ref "R10") (pin "1") (pinfunction "1_1") (pintype "passive"))
      (node (ref "R11") (pin "1") (pinfunction "1_1") (pintype "passive"))
      (node (ref "R12") (pin "1") (pinfunction "1_1") (pintype "passive"))
      (node (ref "R17") (pin "1") (pinfunction "1_1") (pintype "passive"))
      (node (ref "R18") (pin "1") (pinfunction "1_1") (pintype "passive"))
      (node (ref "R19") (pin "1") (pinfunction "1_1") (pintype "passive"))
      (node (ref "R2") (pin "1") (pinfunction "1_1") (pintype "passive"))
      (node (ref "R20") (pin "1") (pinfunction "1_1") (pintype "passive"))
      (node (ref "R25") (pin "1") (pinfunction "1_1") (pintype "passive"))
      (node (ref "R26") (pin "1") (pinfunction "1_1") (pintype "passive"))
      (node (ref "R27") (pin "1") (pinfunction "1_1") (pintype "passive"))
      (node (ref "R28") (pin "1") (pinfunction "1_1") (pintype "passive"))
      (node (ref "R3") (pin "1") (pinfunction "1_1") (pintype "passive"))
      (node (ref "R4") (pin "1") (pinfunction "1_1") (pintype "passive"))
      (node (ref "R9") (pin "1") (pinfunction "1_1") (pintype "passive"))
    )
    (net (code "72") (name "VSYS") (class "Default")
      (node (ref "C5") (pin "2") (pinfunction "2_2") (pintype "passive"))
      (node (ref "C6") (pin "2") (pinfunction "2_2") (pintype "passive"))
      (node (ref "D33") (pin "1") (pinfunction "C_1") (pintype "passive"))
      (node (ref "D38") (pin "1") (pinfunction "C_1") (pintype "passive"))
      (node (ref "R35") (pin "2") (pinfunction "2_2") (pintype "passive"))
      (node (ref "R36") (pin "2") (pinfunction "2_2") (pintype "passive"))
      (node (ref "U1") (pin "39") (pinfunction "VSYS_39") (pintype "passive"))
      (node (ref "U3") (pin "6") (pinfunction "VCCB_6") (pintype "passive"))
      (node (ref "U4") (pin "1") (pinfunction "VDD_1") (pintype "passive"))
    )
    (net (code "73") (name "unconnected-(U1A-ADC0{slash}GP26-Pad31)") (class "Default")
      (node (ref "U1") (pin "31") (pinfunction "ADC0/GP26_31") (pintype "bidirectional"))
    )
    (net (code "74") (name "unconnected-(U1A-ADC1{slash}GP27-Pad32)") (class "Default")
      (node (ref "U1") (pin "32") (pinfunction "ADC1/GP27_32") (pintype "bidirectional"))
    )
    (net (code "75") (name "unconnected-(U1A-ADC2{slash}GP28-Pad34)") (class "Default")
      (node (ref "U1") (pin "34") (pinfunction "ADC2/GP28_34") (pintype "bidirectional"))
    )
    (net (code "76") (name "unconnected-(U1B-(USB)GND-PadTP1)") (class "Default")
      (node (ref "U1") (pin "TP1") (pinfunction "(USB)GND_TP1") (pintype "passive"))
    )
    (net (code "77") (name "unconnected-(U1B-3V3_EN-Pad37)") (class "Default")
      (node (ref "U1") (pin "37") (pinfunction "3V3_EN_37") (pintype "passive"))
    )
    (net (code "78") (name "unconnected-(U1B-ADC_VREF-Pad35)") (class "Default")
      (node (ref "U1") (pin "35") (pinfunction "ADC_VREF_35") (pintype "passive"))
    )
    (net (code "79") (name "unconnected-(U1B-RUN-Pad30)") (class "Default")
      (node (ref "U1") (pin "30") (pinfunction "RUN_30") (pintype "passive"))
    )
    (net (code "80") (name "unconnected-(U1B-USB_D+-PadTP3)") (class "Default")
      (node (ref "U1") (pin "TP3") (pinfunction "USB_D+_TP3") (pintype "passive"))
    )
    (net (code "81") (name "unconnected-(U1B-USB_D--PadTP2)") (class "Default")
      (node (ref "U1") (pin "TP2") (pinfunction "USB_D-_TP2") (pintype "passive"))
    )
    (net (code "82") (name "unconnected-(U1B-VBUS-Pad40)") (class "Default")
      (node (ref "U1") (pin "40") (pinfunction "VBUS_40") (pintype "passive"))
    )
    (net (code "83") (name "unconnected-(U4-DOUT-Pad2)") (class "Default")
      (node (ref "U4") (pin "2") (pinfunction "DOUT_2") (pintype "output"))
    )
  )
)
